# Sheet4.net
KiCad netlist of a schematic drawn in Altium Designer
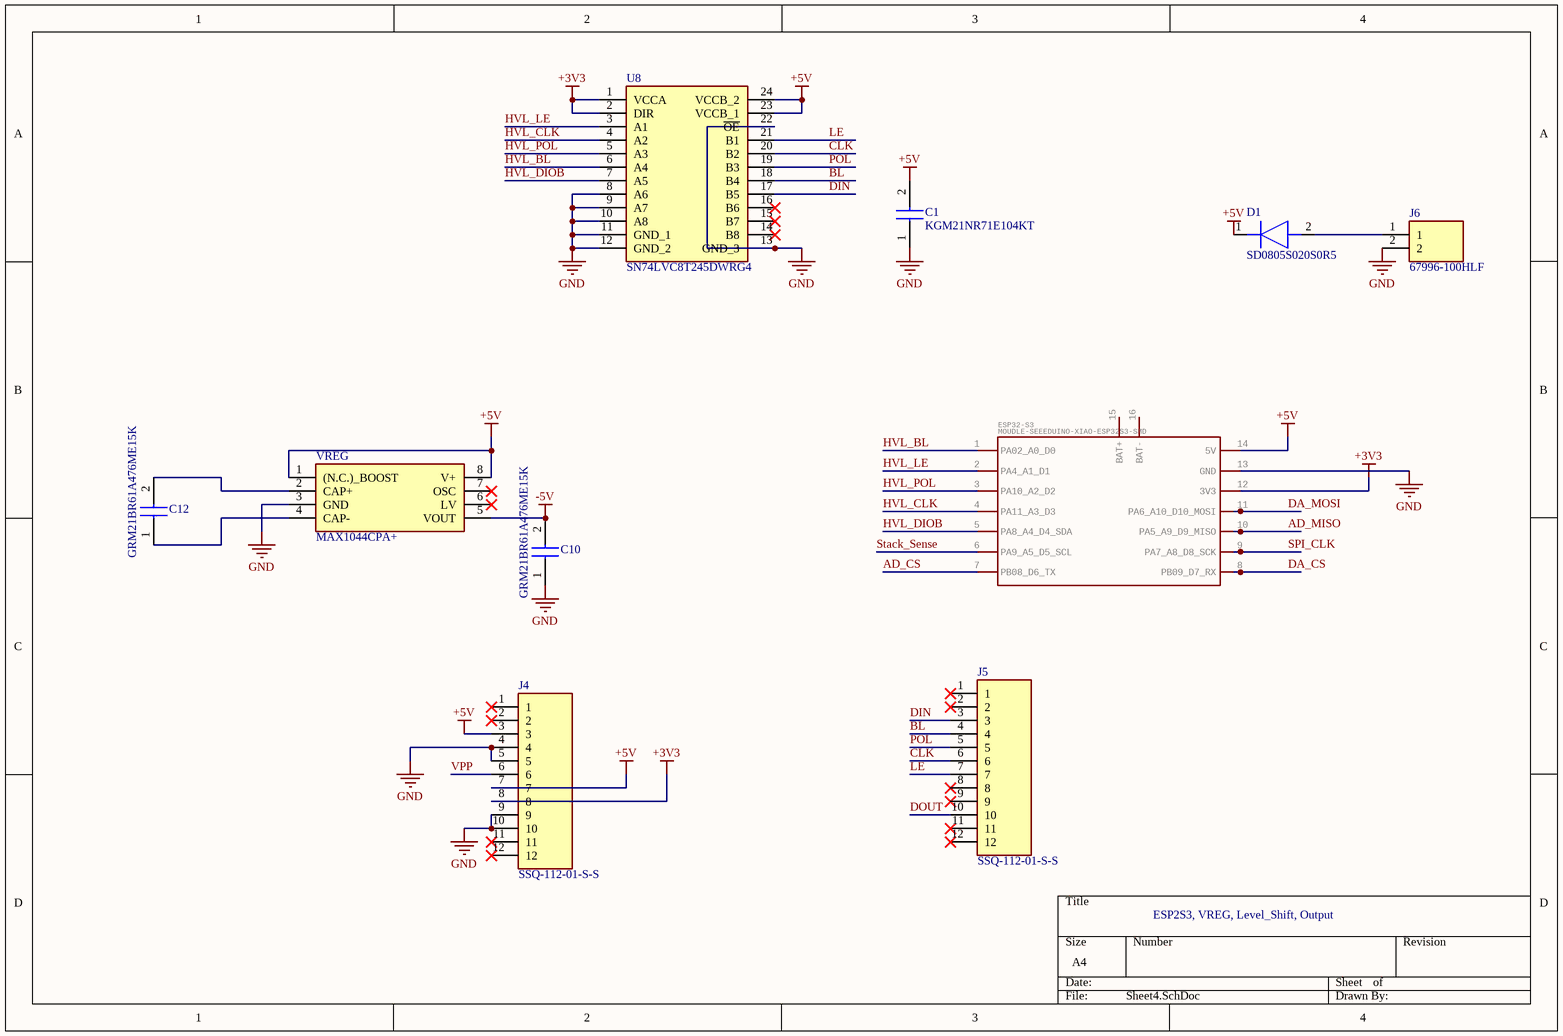
[diagram p0: Sheet4.SchDoc]

(export (version "E")
  (design (tool "Eeschema 10.0.6"))
  (components
    (comp (ref "C1")
      (value "KGM21NR71E104KT")
      (footprint "SamacSys:CAPC2012X100N")
      (description "Capacitor")
      (fields (field (name "MOUSER PART NUMBER") "581-KGM21NR71E104KT"))
      (libsource (lib "*") (part "KGM21NR71E104KT"))
    )
    (comp (ref "C10")
      (value "GRM21BR61A476ME15K")
      (footprint "SamacSys:CAPC2012X100N")
      (description "Capacitor")
      (fields
        (field (name "MANUFACTURER_PART_NUMBER") "KGM21NR71E104KT")
        (field (name "MOUSER PART NUMBER") "581-KGM21NR71E104KT")
      )
      (libsource (lib "*") (part "KGM21NR71E104KT"))
    )
    (comp (ref "C12")
      (value "GRM21BR61A476ME15K")
      (footprint "SamacSys:CAPC2012X100N")
      (description "Capacitor")
      (fields
        (field (name "MANUFACTURER_PART_NUMBER") "KGM21NR71E104KT")
        (field (name "MOUSER PART NUMBER") "581-KGM21NR71E104KT")
      )
      (libsource (lib "*") (part "KGM21NR71E104KT"))
    )
    (comp (ref "D1")
      (value "SD0805S020S0R5")
      (footprint "SamacSys:DIOC2013X100N")
      (description "Diode")
      (fields (field (name "MOUSER PART NUMBER") "581-SD0805S020S0R5"))
      (libsource (lib "*") (part "SD0805S020S0R5"))
    )
    (comp (ref "ESP32-S3")
      (value "MOUDLE-SEEEDUINO-XIAO-ESP32S3-SMD")
      (footprint "MOUDLE14P-2-54-21X17-8MM")
      (fields (field (name "LIBRARYNAME") "Seeed-Studio-XIAO-ESP32S3-footprint-eagle (1)"))
      (libsource (lib "Seeed-Studio-XIAO-ESP32S3-footprint-eagle (1)") (part "MOUDLE-SEEEDUINO-XIAO-ESP32S3-SMD"))
    )
    (comp (ref "J4")
      (value "SSQ-112-01-S-S")
      (footprint "RHDR12W64P254_1X12_3099X241X851P")
      (description "12 Position, .100&quot; Tiger Buy&trade; Socket Strip, Square Tail, Single Row")
      (fields (field (name "MOUSER PART NUMBER") "200-SSQ11201SS"))
      (libsource (lib "SSQ-112-01-S-S") (part "SSQ-112-01-S-S"))
    )
    (comp (ref "J5")
      (value "SSQ-112-01-S-S")
      (footprint "RHDR12W64P254_1X12_3099X241X851P")
      (description "12 Position, .100&quot; Tiger Buy&trade; Socket Strip, Square Tail, Single Row")
      (fields (field (name "MOUSER PART NUMBER") "200-SSQ11201SS"))
      (libsource (lib "SSQ-112-01-S-S") (part "SSQ-112-01-S-S"))
    )
    (comp (ref "J6")
      (value "67996-100HLF")
      (footprint "HDRV2W67P254_2X1_254X483X858P")
      (libsource (lib "67996-100HLF") (part "67996-100HLF"))
    )
    (comp (ref "U8")
      (value "SN74LVC8T245DWRG4")
      (footprint "SamacSys:SOIC127P1030X265-24N")
      (description "Integrated Circuit")
      (fields (field (name "MOUSER PART NUMBER") "595-74LVC8T245DWRG4"))
      (libsource (lib "SamacSys") (part "SN74LVC8T245DWRG4"))
    )
    (comp (ref "VREG")
      (value "MAX1044CPA+")
      (footprint "SamacSys:DIP794W56P254L938H457Q8N")
      (description "Power Supply")
      (fields (field (name "MOUSER PART NUMBER") "700-MAX1044CPA"))
      (libsource (lib "*") (part "MAX1044CPA+"))
    )
  )
  (nets
    (net (code "1") (name "+3V3") (class "Default")
      (node (ref "ESP32-S3") (pin "12") (pinfunction "3V3_12") (pintype "bidirectional"))
      (node (ref "J4") (pin "8") (pinfunction "8_8") (pintype "passive"))
      (node (ref "U8") (pin "1") (pinfunction "VCCA_1") (pintype "passive"))
      (node (ref "U8") (pin "2") (pinfunction "DIR_2") (pintype "passive"))
    )
    (net (code "2") (name "+5V") (class "Default")
      (node (ref "C1") (pin "2") (pinfunction "2_2") (pintype "passive"))
      (node (ref "D1") (pin "1") (pinfunction "K_1") (pintype "passive"))
      (node (ref "ESP32-S3") (pin "14") (pinfunction "5V_14") (pintype "bidirectional"))
      (node (ref "J4") (pin "3") (pinfunction "3_3") (pintype "passive"))
      (node (ref "J4") (pin "7") (pinfunction "7_7") (pintype "passive"))
      (node (ref "U8") (pin "23") (pinfunction "VCCB_1_23") (pintype "passive"))
      (node (ref "U8") (pin "24") (pinfunction "VCCB_2_24") (pintype "passive"))
      (node (ref "VREG") (pin "1") (pinfunction "(N.C.)_BOOST_1") (pintype "passive"))
      (node (ref "VREG") (pin "8") (pinfunction "V+_8") (pintype "passive"))
    )
    (net (code "3") (name "-5V") (class "Default")
      (node (ref "C10") (pin "2") (pinfunction "2_2") (pintype "passive"))
      (node (ref "VREG") (pin "5") (pinfunction "VOUT_5") (pintype "passive"))
    )
    (net (code "4") (name "/AD_CS") (class "Default")
      (node (ref "ESP32-S3") (pin "7") (pinfunction "PB08_D6_TX_7") (pintype "bidirectional"))
    )
    (net (code "5") (name "/AD_MISO") (class "Default")
      (node (ref "ESP32-S3") (pin "10") (pinfunction "PA5_A9_D9_MISO_10") (pintype "bidirectional"))
    )
    (net (code "6") (name "/BL") (class "Default")
      (node (ref "J5") (pin "4") (pinfunction "4_4") (pintype "passive"))
      (node (ref "U8") (pin "18") (pinfunction "B4_18") (pintype "passive"))
    )
    (net (code "7") (name "/CLK") (class "Default")
      (node (ref "J5") (pin "6") (pinfunction "6_6") (pintype "passive"))
      (node (ref "U8") (pin "20") (pinfunction "B2_20") (pintype "passive"))
    )
    (net (code "8") (name "/DA_CS") (class "Default")
      (node (ref "ESP32-S3") (pin "8") (pinfunction "PB09_D7_RX_8") (pintype "bidirectional"))
    )
    (net (code "9") (name "/DA_MOSI") (class "Default")
      (node (ref "ESP32-S3") (pin "11") (pinfunction "PA6_A10_D10_MOSI_11") (pintype "bidirectional"))
    )
    (net (code "10") (name "/DIN") (class "Default")
      (node (ref "J5") (pin "3") (pinfunction "3_3") (pintype "passive"))
      (node (ref "U8") (pin "17") (pinfunction "B5_17") (pintype "passive"))
    )
    (net (code "11") (name "/DOUT") (class "Default")
      (node (ref "J5") (pin "10") (pinfunction "10_10") (pintype "passive"))
    )
    (net (code "12") (name "/HVL_BL") (class "Default")
      (node (ref "ESP32-S3") (pin "1") (pinfunction "PA02_A0_D0_1") (pintype "bidirectional"))
      (node (ref "U8") (pin "6") (pinfunction "A4_6") (pintype "passive"))
    )
    (net (code "13") (name "/HVL_CLK") (class "Default")
      (node (ref "ESP32-S3") (pin "4") (pinfunction "PA11_A3_D3_4") (pintype "bidirectional"))
      (node (ref "U8") (pin "4") (pinfunction "A2_4") (pintype "passive"))
    )
    (net (code "14") (name "/HVL_DIOB") (class "Default")
      (node (ref "ESP32-S3") (pin "5") (pinfunction "PA8_A4_D4_SDA_5") (pintype "bidirectional"))
      (node (ref "U8") (pin "7") (pinfunction "A5_7") (pintype "passive"))
    )
    (net (code "15") (name "/HVL_LE") (class "Default")
      (node (ref "ESP32-S3") (pin "2") (pinfunction "PA4_A1_D1_2") (pintype "bidirectional"))
      (node (ref "U8") (pin "3") (pinfunction "A1_3") (pintype "passive"))
    )
    (net (code "16") (name "/HVL_POL") (class "Default")
      (node (ref "ESP32-S3") (pin "3") (pinfunction "PA10_A2_D2_3") (pintype "bidirectional"))
      (node (ref "U8") (pin "5") (pinfunction "A3_5") (pintype "passive"))
    )
    (net (code "17") (name "/LE") (class "Default")
      (node (ref "J5") (pin "7") (pinfunction "7_7") (pintype "passive"))
      (node (ref "U8") (pin "21") (pinfunction "B1_21") (pintype "passive"))
    )
    (net (code "18") (name "/POL") (class "Default")
      (node (ref "J5") (pin "5") (pinfunction "5_5") (pintype "passive"))
      (node (ref "U8") (pin "19") (pinfunction "B3_19") (pintype "passive"))
    )
    (net (code "19") (name "/SPI_CLK") (class "Default")
      (node (ref "ESP32-S3") (pin "9") (pinfunction "PA7_A8_D8_SCK_9") (pintype "bidirectional"))
    )
    (net (code "20") (name "/Stack_Sense") (class "Default")
      (node (ref "ESP32-S3") (pin "6") (pinfunction "PA9_A5_D5_SCL_6") (pintype "bidirectional"))
    )
    (net (code "21") (name "/VPP") (class "Default")
      (node (ref "J4") (pin "6") (pinfunction "6_6") (pintype "passive"))
    )
    (net (code "22") (name "GND") (class "Default")
      (node (ref "C1") (pin "1") (pinfunction "1_1") (pintype "passive"))
      (node (ref "C10") (pin "1") (pinfunction "1_1") (pintype "passive"))
      (node (ref "ESP32-S3") (pin "13") (pinfunction "GND_13") (pintype "bidirectional"))
      (node (ref "J4") (pin "10") (pinfunction "10_10") (pintype "passive"))
      (node (ref "J4") (pin "4") (pinfunction "4_4") (pintype "passive"))
      (node (ref "J4") (pin "5") (pinfunction "5_5") (pintype "passive"))
      (node (ref "J4") (pin "9") (pinfunction "9_9") (pintype "passive"))
      (node (ref "J6") (pin "2") (pinfunction "2_2") (pintype "passive"))
      (node (ref "U8") (pin "10") (pinfunction "A8_10") (pintype "passive"))
      (node (ref "U8") (pin "11") (pinfunction "GND_1_11") (pintype "passive"))
      (node (ref "U8") (pin "12") (pinfunction "GND_2_12") (pintype "passive"))
      (node (ref "U8") (pin "13") (pinfunction "GND_3_13") (pintype "passive"))
      (node (ref "U8") (pin "22") (pinfunction "~{OE}_22") (pintype "passive"))
      (node (ref "U8") (pin "8") (pinfunction "A6_8") (pintype "passive"))
      (node (ref "U8") (pin "9") (pinfunction "A7_9") (pintype "passive"))
      (node (ref "VREG") (pin "3") (pinfunction "GND_3") (pintype "passive"))
    )
    (net (code "23") (name "Net-(D1-A)") (class "Default")
      (node (ref "D1") (pin "2") (pinfunction "A_2") (pintype "passive"))
      (node (ref "J6") (pin "1") (pinfunction "1_1") (pintype "passive"))
    )
    (net (code "24") (name "Net-(VREG-CAP+)") (class "Default")
      (node (ref "C12") (pin "2") (pinfunction "2_2") (pintype "passive"))
      (node (ref "VREG") (pin "2") (pinfunction "CAP+_2") (pintype "passive"))
    )
    (net (code "25") (name "Net-(VREG-CAP-)") (class "Default")
      (node (ref "C12") (pin "1") (pinfunction "1_1") (pintype "passive"))
      (node (ref "VREG") (pin "4") (pinfunction "CAP-_4") (pintype "passive"))
    )
    (net (code "26") (name "unconnected-(ESP32-S3-BAT+-Pad15)") (class "Default")
      (node (ref "ESP32-S3") (pin "15") (pinfunction "BAT+_15") (pintype "bidirectional"))
    )
    (net (code "27") (name "unconnected-(ESP32-S3-BAT--Pad16)") (class "Default")
      (node (ref "ESP32-S3") (pin "16") (pinfunction "BAT-_16") (pintype "bidirectional"))
    )
    (net (code "28") (name "unconnected-(J4-Pad1)") (class "Default")
      (node (ref "J4") (pin "1") (pinfunction "1_1") (pintype "passive+no_connect"))
    )
    (net (code "29") (name "unconnected-(J4-Pad2)") (class "Default")
      (node (ref "J4") (pin "2") (pinfunction "2_2") (pintype "passive+no_connect"))
    )
    (net (code "30") (name "unconnected-(J4-Pad11)") (class "Default")
      (node (ref "J4") (pin "11") (pinfunction "11_11") (pintype "passive+no_connect"))
    )
    (net (code "31") (name "unconnected-(J4-Pad12)") (class "Default")
      (node (ref "J4") (pin "12") (pinfunction "12_12") (pintype "passive+no_connect"))
    )
    (net (code "32") (name "unconnected-(J5-Pad1)") (class "Default")
      (node (ref "J5") (pin "1") (pinfunction "1_1") (pintype "passive+no_connect"))
    )
    (net (code "33") (name "unconnected-(J5-Pad2)") (class "Default")
      (node (ref "J5") (pin "2") (pinfunction "2_2") (pintype "passive+no_connect"))
    )
    (net (code "34") (name "unconnected-(J5-Pad8)") (class "Default")
      (node (ref "J5") (pin "8") (pinfunction "8_8") (pintype "passive+no_connect"))
    )
    (net (code "35") (name "unconnected-(J5-Pad9)") (class "Default")
      (node (ref "J5") (pin "9") (pinfunction "9_9") (pintype "passive+no_connect"))
    )
    (net (code "36") (name "unconnected-(J5-Pad11)") (class "Default")
      (node (ref "J5") (pin "11") (pinfunction "11_11") (pintype "passive+no_connect"))
    )
    (net (code "37") (name "unconnected-(J5-Pad12)") (class "Default")
      (node (ref "J5") (pin "12") (pinfunction "12_12") (pintype "passive+no_connect"))
    )
    (net (code "38") (name "unconnected-(U8-B6-Pad16)") (class "Default")
      (node (ref "U8") (pin "16") (pinfunction "B6_16") (pintype "passive+no_connect"))
    )
    (net (code "39") (name "unconnected-(U8-B7-Pad15)") (class "Default")
      (node (ref "U8") (pin "15") (pinfunction "B7_15") (pintype "passive+no_connect"))
    )
    (net (code "40") (name "unconnected-(U8-B8-Pad14)") (class "Default")
      (node (ref "U8") (pin "14") (pinfunction "B8_14") (pintype "passive+no_connect"))
    )
    (net (code "41") (name "unconnected-(VREG-LV-Pad6)") (class "Default")
      (node (ref "VREG") (pin "6") (pinfunction "LV_6") (pintype "passive+no_connect"))
    )
    (net (code "42") (name "unconnected-(VREG-OSC-Pad7)") (class "Default")
      (node (ref "VREG") (pin "7") (pinfunction "OSC_7") (pintype "passive+no_connect"))
    )
  )
)
